# usb-485.net
KiCad netlist of a schematic drawn in EAGLE
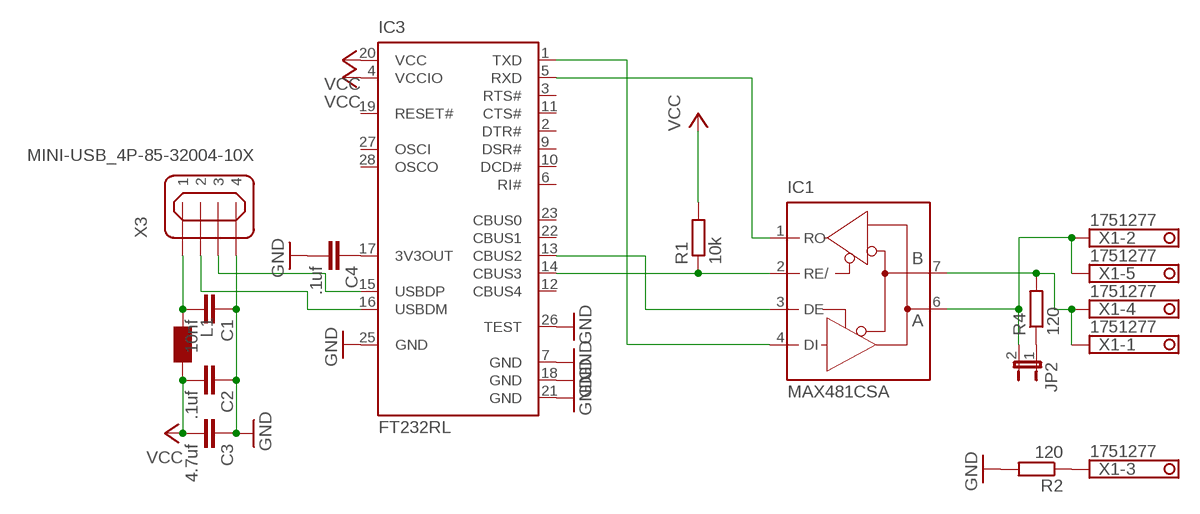
[diagram p0: schematic, sheet 1]

(export (version "E")
  (design (tool "Eeschema 10.0.6"))
  (components
    (comp (ref "C1")
      (value "10nf")
      (footprint "eagle-import:C0805")
      (libsource (lib "eagle-import") (part "C-EUC0805"))
    )
    (comp (ref "C2")
      (value ".1uf")
      (footprint "eagle-import:C1206")
      (libsource (lib "eagle-import") (part "C-EUC1206"))
    )
    (comp (ref "C3")
      (value "4.7uf")
      (footprint "eagle-import:C1206")
      (libsource (lib "eagle-import") (part "C-EUC1206"))
    )
    (comp (ref "C4")
      (value ".1uf")
      (footprint "eagle-import:C1206")
      (libsource (lib "eagle-import") (part "C-EUC1206"))
    )
    (comp (ref "IC1")
      (value "MAX481CSA")
      (footprint "eagle-import:SO08")
      (fields (field (name "MF") "MAXIM"))
      (libsource (lib "eagle-import") (part "MAX481CSA"))
    )
    (comp (ref "IC3")
      (value "FT232RL")
      (footprint "eagle-import:SSOP28")
      (libsource (lib "eagle-import") (part "FT232RL"))
    )
    (comp (ref "JP2")
      (value "JP1E")
      (footprint "eagle-import:JP1")
      (libsource (lib "eagle-import") (part "JP1E"))
    )
    (comp (ref "L1")
      (value "WE-CBF_1206")
      (footprint "eagle-import:1206")
      (libsource (lib "eagle-import") (part "WE-CBF_1206"))
    )
    (comp (ref "R1")
      (value "10k")
      (footprint "eagle-import:0207_10")
      (libsource (lib "eagle-import") (part "R-EU_0207/10"))
    )
    (comp (ref "R2")
      (value "120")
      (footprint "eagle-import:0207_10")
      (libsource (lib "eagle-import") (part "R-EU_0207/10"))
    )
    (comp (ref "R4")
      (value "120")
      (footprint "eagle-import:0207_10")
      (libsource (lib "eagle-import") (part "R-EU_0207/10"))
    )
    (comp (ref "X1")
      (value "1751277")
      (footprint "eagle-import:1751277")
      (libsource (lib "eagle-import") (part "1751277"))
    )
    (comp (ref "X3")
      (value "MINI-USB_4P-85-32004-10X")
      (footprint "eagle-import:85-32004-10X")
      (libsource (lib "eagle-import") (part "MINI-USB_4P-85-32004-10X"))
    )
  )
  (nets
    (net (code "1") (name "GND") (class "Default")
      (node (ref "C1") (pin "1") (pinfunction "1_1") (pintype "passive"))
      (node (ref "C2") (pin "1") (pinfunction "1_1") (pintype "passive"))
      (node (ref "C3") (pin "1") (pinfunction "1_1") (pintype "passive"))
      (node (ref "C4") (pin "2") (pinfunction "2_2") (pintype "passive"))
      (node (ref "IC3") (pin "18") (pinfunction "GND_18") (pintype "input"))
      (node (ref "IC3") (pin "21") (pinfunction "GND_21") (pintype "input"))
      (node (ref "IC3") (pin "25") (pinfunction "GND_25") (pintype "input"))
      (node (ref "IC3") (pin "26") (pinfunction "TEST_26") (pintype "input"))
      (node (ref "IC3") (pin "7") (pinfunction "GND_7") (pintype "input"))
      (node (ref "R2") (pin "2") (pinfunction "2_2") (pintype "passive"))
      (node (ref "X3") (pin "4") (pinfunction "4_4") (pintype "passive"))
    )
    (net (code "2") (name "Net-(C1-Pad2)") (class "Default")
      (node (ref "C1") (pin "2") (pinfunction "2_2") (pintype "passive"))
      (node (ref "L1") (pin "1") (pinfunction "1_1") (pintype "passive"))
      (node (ref "X3") (pin "1") (pinfunction "1_1") (pintype "passive"))
    )
    (net (code "3") (name "Net-(IC1A-A)") (class "Default")
      (node (ref "IC1") (pin "6") (pinfunction "A_6") (pintype "passive"))
      (node (ref "JP2") (pin "2") (pinfunction "2_2") (pintype "passive"))
      (node (ref "X1") (pin "2") (pinfunction "K_2") (pintype "passive"))
      (node (ref "X1") (pin "5") (pinfunction "K_5") (pintype "passive"))
    )
    (net (code "4") (name "Net-(IC1A-B)") (class "Default")
      (node (ref "IC1") (pin "7") (pinfunction "B_7") (pintype "passive"))
      (node (ref "R4") (pin "2") (pinfunction "2_2") (pintype "passive"))
      (node (ref "X1") (pin "1") (pinfunction "K_1") (pintype "passive"))
      (node (ref "X1") (pin "4") (pinfunction "K_4") (pintype "passive"))
    )
    (net (code "5") (name "Net-(IC1A-DE)") (class "Default")
      (node (ref "IC1") (pin "3") (pinfunction "DE_3") (pintype "input"))
      (node (ref "IC3") (pin "13") (pinfunction "CBUS2_13") (pintype "input"))
    )
    (net (code "6") (name "Net-(IC1A-DI)") (class "Default")
      (node (ref "IC1") (pin "4") (pinfunction "DI_4") (pintype "input"))
      (node (ref "IC3") (pin "1") (pinfunction "TXD_1") (pintype "input"))
    )
    (net (code "7") (name "Net-(IC1A-RE{slash})") (class "Default")
      (node (ref "IC1") (pin "2") (pinfunction "RE/_2") (pintype "input"))
      (node (ref "IC3") (pin "14") (pinfunction "CBUS3_14") (pintype "input"))
      (node (ref "R1") (pin "1") (pinfunction "1_1") (pintype "passive"))
    )
    (net (code "8") (name "Net-(IC1A-RO)") (class "Default")
      (node (ref "IC1") (pin "1") (pinfunction "RO_1") (pintype "output"))
      (node (ref "IC3") (pin "5") (pinfunction "RXD_5") (pintype "input"))
    )
    (net (code "9") (name "Net-(IC3-3V3OUT)") (class "Default")
      (node (ref "C4") (pin "1") (pinfunction "1_1") (pintype "passive"))
      (node (ref "IC3") (pin "17") (pinfunction "3V3OUT_17") (pintype "input"))
    )
    (net (code "10") (name "Net-(IC3-USBDM)") (class "Default")
      (node (ref "IC3") (pin "16") (pinfunction "USBDM_16") (pintype "input"))
      (node (ref "X3") (pin "2") (pinfunction "2_2") (pintype "passive"))
    )
    (net (code "11") (name "Net-(IC3-USBDP)") (class "Default")
      (node (ref "IC3") (pin "15") (pinfunction "USBDP_15") (pintype "input"))
      (node (ref "X3") (pin "3") (pinfunction "3_3") (pintype "passive"))
    )
    (net (code "12") (name "Net-(JP2-Pad1)") (class "Default")
      (node (ref "JP2") (pin "1") (pinfunction "1_1") (pintype "passive"))
      (node (ref "R4") (pin "1") (pinfunction "1_1") (pintype "passive"))
    )
    (net (code "13") (name "Net-(X1C-K)") (class "Default")
      (node (ref "R2") (pin "1") (pinfunction "1_1") (pintype "passive"))
      (node (ref "X1") (pin "3") (pinfunction "K_3") (pintype "passive"))
    )
    (net (code "14") (name "VCC") (class "Default")
      (node (ref "C2") (pin "2") (pinfunction "2_2") (pintype "passive"))
      (node (ref "C3") (pin "2") (pinfunction "2_2") (pintype "passive"))
      (node (ref "IC3") (pin "20") (pinfunction "VCC_20") (pintype "input"))
      (node (ref "IC3") (pin "4") (pinfunction "VCCIO_4") (pintype "input"))
      (node (ref "L1") (pin "2") (pinfunction "2_2") (pintype "passive"))
      (node (ref "R1") (pin "2") (pinfunction "2_2") (pintype "passive"))
    )
    (net (code "15") (name "unconnected-(IC3-CBUS0-Pad23)") (class "Default")
      (node (ref "IC3") (pin "23") (pinfunction "CBUS0_23") (pintype "input"))
    )
    (net (code "16") (name "unconnected-(IC3-CBUS1-Pad22)") (class "Default")
      (node (ref "IC3") (pin "22") (pinfunction "CBUS1_22") (pintype "input"))
    )
    (net (code "17") (name "unconnected-(IC3-CBUS4-Pad12)") (class "Default")
      (node (ref "IC3") (pin "12") (pinfunction "CBUS4_12") (pintype "input"))
    )
    (net (code "18") (name "unconnected-(IC3-CTS#-Pad11)") (class "Default")
      (node (ref "IC3") (pin "11") (pinfunction "CTS#_11") (pintype "input"))
    )
    (net (code "19") (name "unconnected-(IC3-DCD#-Pad10)") (class "Default")
      (node (ref "IC3") (pin "10") (pinfunction "DCD#_10") (pintype "input"))
    )
    (net (code "20") (name "unconnected-(IC3-DSR#-Pad9)") (class "Default")
      (node (ref "IC3") (pin "9") (pinfunction "DSR#_9") (pintype "input"))
    )
    (net (code "21") (name "unconnected-(IC3-DTR#-Pad2)") (class "Default")
      (node (ref "IC3") (pin "2") (pinfunction "DTR#_2") (pintype "input"))
    )
    (net (code "22") (name "unconnected-(IC3-OSCI-Pad27)") (class "Default")
      (node (ref "IC3") (pin "27") (pinfunction "OSCI_27") (pintype "input"))
    )
    (net (code "23") (name "unconnected-(IC3-OSCO-Pad28)") (class "Default")
      (node (ref "IC3") (pin "28") (pinfunction "OSCO_28") (pintype "input"))
    )
    (net (code "24") (name "unconnected-(IC3-RESET#-Pad19)") (class "Default")
      (node (ref "IC3") (pin "19") (pinfunction "RESET#_19") (pintype "input"))
    )
    (net (code "25") (name "unconnected-(IC3-RI#-Pad6)") (class "Default")
      (node (ref "IC3") (pin "6") (pinfunction "RI#_6") (pintype "input"))
    )
    (net (code "26") (name "unconnected-(IC3-RTS#-Pad3)") (class "Default")
      (node (ref "IC3") (pin "3") (pinfunction "RTS#_3") (pintype "input"))
    )
  )
)
